# ptc.net
KiCad netlist of a schematic drawn in EasyEDA Pro
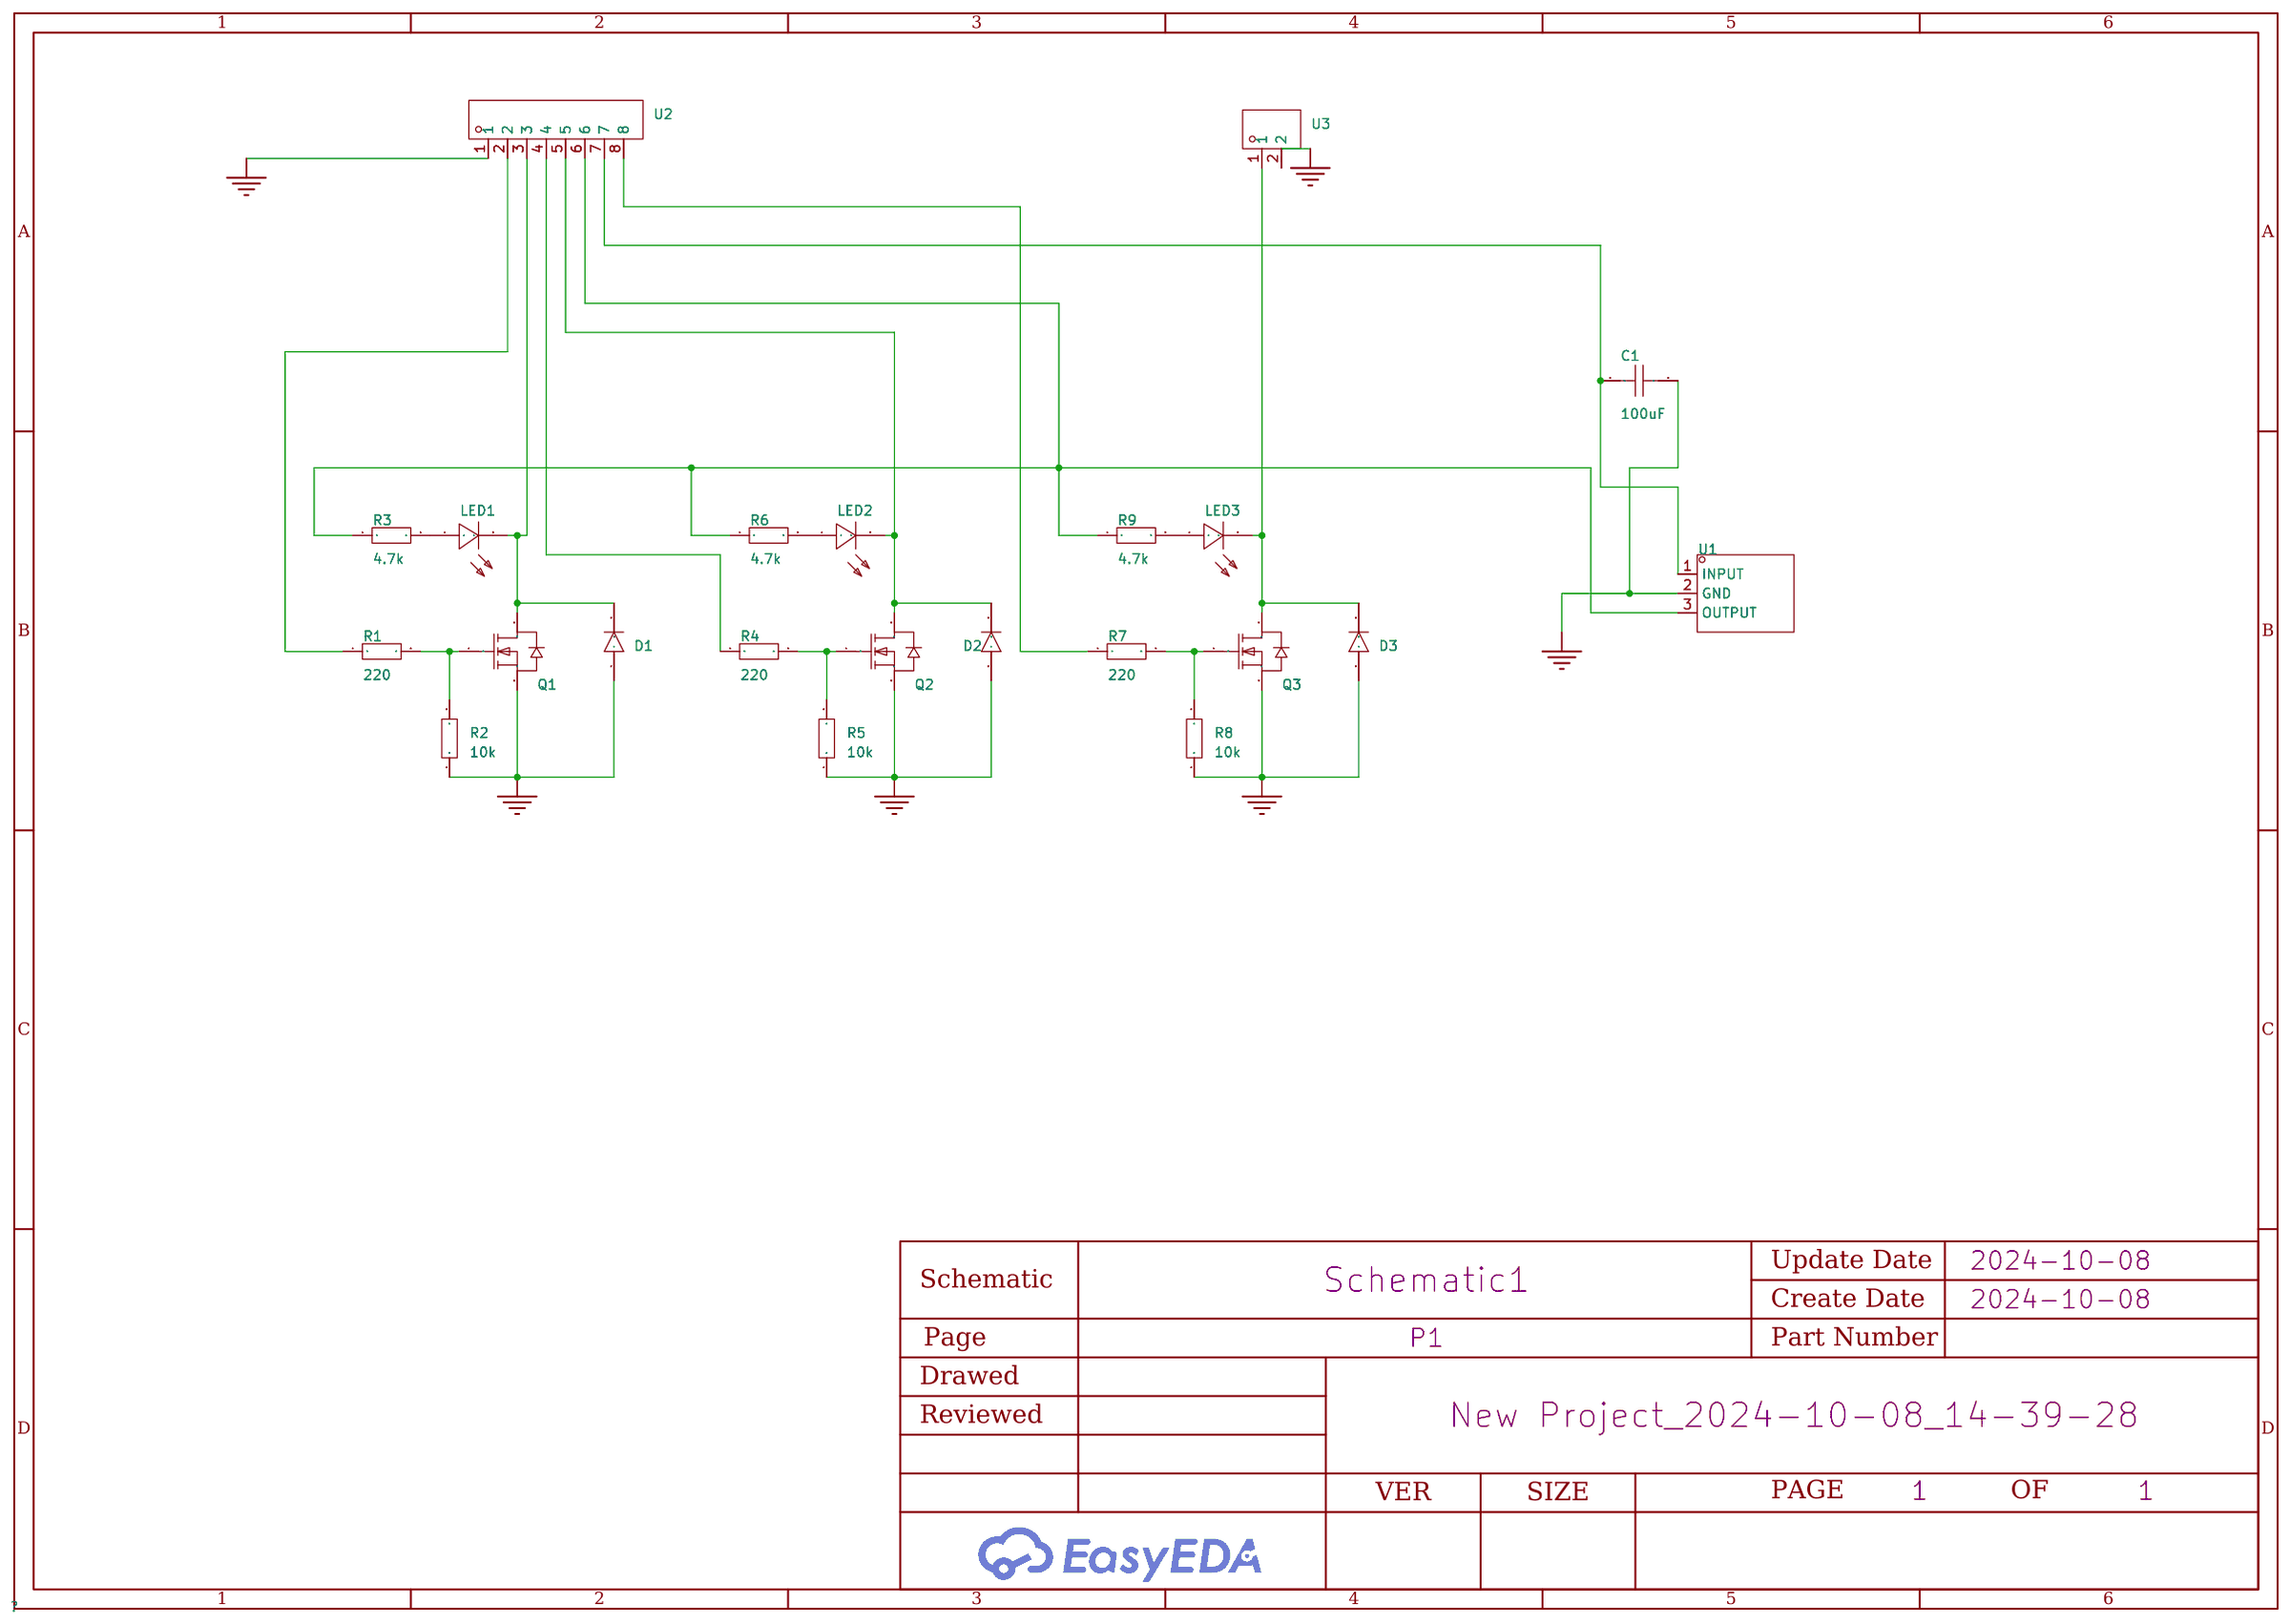
[diagram p0: schematic sheet]

(export (version "E")
  (design (tool "Eeschema 10.0.6"))
  (components
    (comp (ref "C1")
      (value "100uF")
      (footprint "easyedapro:C0603")
      (libsource (lib "easyedapro") (part "CapAcitance"))
    )
    (comp (ref "D1")
      (value "~")
      (footprint "easyedapro:DO-41_BD2.4-L4.7-P8.70-D0.9-RD")
      (fields (field (name "Manufacturer Part") "1N4007") (field (name "Manufacturer") "星海"))
      (libsource (lib "easyedapro") (part "1N4007-C84641"))
    )
    (comp (ref "D2")
      (value "~")
      (footprint "easyedapro:DO-41_BD2.4-L4.7-P8.70-D0.9-RD")
      (fields (field (name "Manufacturer Part") "1N4007") (field (name "Manufacturer") "星海"))
      (libsource (lib "easyedapro") (part "1N4007-C84641"))
    )
    (comp (ref "D3")
      (value "~")
      (footprint "easyedapro:DO-41_BD2.4-L4.7-P8.70-D0.9-RD")
      (fields (field (name "Manufacturer Part") "1N4007") (field (name "Manufacturer") "星海"))
      (libsource (lib "easyedapro") (part "1N4007-C84641"))
    )
    (comp (ref "LED1")
      (value "~")
      (footprint "easyedapro:LED0603-R-RD_RED")
      (fields
        (field (name "Manufacturer Part") "TJ-S1608SW6TGLC2R-A5")
        (field (name "Manufacturer") "TOGIALED(台湾统佳)")
      )
      (libsource (lib "easyedapro") (part "TJ-S1608SW6TGLC2R-A5"))
    )
    (comp (ref "LED2")
      (value "~")
      (footprint "easyedapro:LED0603-R-RD_RED")
      (fields
        (field (name "Manufacturer Part") "TJ-S1608SW6TGLC2R-A5")
        (field (name "Manufacturer") "TOGIALED(台湾统佳)")
      )
      (libsource (lib "easyedapro") (part "TJ-S1608SW6TGLC2R-A5"))
    )
    (comp (ref "LED3")
      (value "~")
      (footprint "easyedapro:LED0603-R-RD_RED")
      (fields
        (field (name "Manufacturer Part") "TJ-S1608SW6TGLC2R-A5")
        (field (name "Manufacturer") "TOGIALED(台湾统佳)")
      )
      (libsource (lib "easyedapro") (part "TJ-S1608SW6TGLC2R-A5"))
    )
    (comp (ref "Q1")
      (value "~")
      (footprint "easyedapro:TO-220-3_L10.0-W4.5-P2.54-L")
      (fields (field (name "Manufacturer Part") "IRFZ44NPBF") (field (name "Manufacturer") "Infineon(英飞凌)"))
      (libsource (lib "easyedapro") (part "IRFZ44NPBF"))
    )
    (comp (ref "Q2")
      (value "~")
      (footprint "easyedapro:TO-220-3_L10.0-W4.5-P2.54-L")
      (fields (field (name "Manufacturer Part") "IRFZ44NPBF") (field (name "Manufacturer") "Infineon(英飞凌)"))
      (libsource (lib "easyedapro") (part "IRFZ44NPBF"))
    )
    (comp (ref "Q3")
      (value "~")
      (footprint "easyedapro:TO-220-3_L10.0-W4.5-P2.54-L")
      (fields (field (name "Manufacturer Part") "IRFZ44NPBF") (field (name "Manufacturer") "Infineon(英飞凌)"))
      (libsource (lib "easyedapro") (part "IRFZ44NPBF"))
    )
    (comp (ref "R1")
      (value "220")
      (footprint "easyedapro:R0603")
      (fields
        (field (name "Manufacturer Part") "MFR0W8F1002A50")
        (field (name "Manufacturer") "UNI-ROYAL(厚声)")
      )
      (libsource (lib "easyedapro") (part "电阻"))
    )
    (comp (ref "R2")
      (value "10k")
      (footprint "easyedapro:R0603")
      (fields
        (field (name "Manufacturer Part") "MFR0W8F1002A50")
        (field (name "Manufacturer") "UNI-ROYAL(厚声)")
      )
      (libsource (lib "easyedapro") (part "电阻"))
    )
    (comp (ref "R3") (value "4.7k") (footprint "easyedapro:R0603") (libsource (lib "easyedapro") (part "电阻")))
    (comp (ref "R4")
      (value "220")
      (footprint "easyedapro:R0603")
      (fields
        (field (name "Manufacturer Part") "MFR0W8F1002A50")
        (field (name "Manufacturer") "UNI-ROYAL(厚声)")
      )
      (libsource (lib "easyedapro") (part "电阻"))
    )
    (comp (ref "R5")
      (value "10k")
      (footprint "easyedapro:R0603")
      (fields
        (field (name "Manufacturer Part") "MFR0W8F1002A50")
        (field (name "Manufacturer") "UNI-ROYAL(厚声)")
      )
      (libsource (lib "easyedapro") (part "电阻"))
    )
    (comp (ref "R6") (value "4.7k") (footprint "easyedapro:R0603") (libsource (lib "easyedapro") (part "电阻")))
    (comp (ref "R7")
      (value "220")
      (footprint "easyedapro:R0603")
      (fields
        (field (name "Manufacturer Part") "MFR0W8F1002A50")
        (field (name "Manufacturer") "UNI-ROYAL(厚声)")
      )
      (libsource (lib "easyedapro") (part "电阻"))
    )
    (comp (ref "R8")
      (value "10k")
      (footprint "easyedapro:R0603")
      (fields
        (field (name "Manufacturer Part") "MFR0W8F1002A50")
        (field (name "Manufacturer") "UNI-ROYAL(厚声)")
      )
      (libsource (lib "easyedapro") (part "电阻"))
    )
    (comp (ref "R9") (value "4.7k") (footprint "easyedapro:R0603") (libsource (lib "easyedapro") (part "电阻")))
    (comp (ref "U1")
      (value "~")
      (footprint "easyedapro:TO-252-2_L6.6-W6.1-P4.57-LS9.9-BR-CW")
      (fields (field (name "Manufacturer Part") "MC7812BDTG") (field (name "Manufacturer") "onsemi(安森美)"))
      (libsource (lib "easyedapro") (part "MC7812BDTG"))
    )
    (comp (ref "U2")
      (value "~")
      (footprint "easyedapro:CONN-TH_8P-P5.00_DB128V-5.0-8P")
      (fields
        (field (name "Manufacturer Part") "DB128V-5.0-8P-GN-S")
        (field (name "Manufacturer") "DIBO(地博电气)")
      )
      (libsource (lib "easyedapro") (part "DB128V-5.0-8P"))
    )
    (comp (ref "U3")
      (value "~")
      (footprint "easyedapro:CONN-TH_2P-P5.00_DB128V-5.0-2P")
      (fields
        (field (name "Manufacturer Part") "DB128V-5.0-2P-GN-S")
        (field (name "Manufacturer") "DIBO(地博电气)")
      )
      (libsource (lib "easyedapro") (part "DB128V-5.0-2P"))
    )
  )
  (nets
    (net (code "1") (name "GND") (class "Default")
      (node (ref "C1") (pin "2") (pinfunction "2_2") (pintype "input"))
      (node (ref "D1") (pin "2") (pinfunction "A_2") (pintype "input"))
      (node (ref "D2") (pin "2") (pinfunction "A_2") (pintype "input"))
      (node (ref "D3") (pin "2") (pinfunction "A_2") (pintype "input"))
      (node (ref "Q1") (pin "3") (pinfunction "S_3") (pintype "input"))
      (node (ref "Q2") (pin "3") (pinfunction "S_3") (pintype "input"))
      (node (ref "Q3") (pin "3") (pinfunction "S_3") (pintype "input"))
      (node (ref "R2") (pin "1") (pinfunction "1_1") (pintype "input"))
      (node (ref "R5") (pin "1") (pinfunction "1_1") (pintype "input"))
      (node (ref "R8") (pin "1") (pinfunction "1_1") (pintype "input"))
      (node (ref "U1") (pin "2") (pinfunction "GND_2") (pintype "input"))
      (node (ref "U2") (pin "1") (pinfunction "1_1") (pintype "input"))
      (node (ref "U3") (pin "2") (pinfunction "2_2") (pintype "input"))
    )
    (net (code "2") (name "Net-(D1-C)") (class "Default")
      (node (ref "D1") (pin "1") (pinfunction "C_1") (pintype "input"))
      (node (ref "LED1") (pin "2") (pinfunction "K_2") (pintype "input"))
      (node (ref "Q1") (pin "2") (pinfunction "D_2") (pintype "input"))
      (node (ref "U2") (pin "3") (pinfunction "3_3") (pintype "input"))
    )
    (net (code "3") (name "Net-(D2-C)") (class "Default")
      (node (ref "D2") (pin "1") (pinfunction "C_1") (pintype "input"))
      (node (ref "LED2") (pin "2") (pinfunction "K_2") (pintype "input"))
      (node (ref "Q2") (pin "2") (pinfunction "D_2") (pintype "input"))
      (node (ref "U2") (pin "5") (pinfunction "5_5") (pintype "input"))
    )
    (net (code "4") (name "Net-(D3-C)") (class "Default")
      (node (ref "D3") (pin "1") (pinfunction "C_1") (pintype "input"))
      (node (ref "LED3") (pin "2") (pinfunction "K_2") (pintype "input"))
      (node (ref "Q3") (pin "2") (pinfunction "D_2") (pintype "input"))
      (node (ref "U3") (pin "1") (pinfunction "1_1") (pintype "input"))
    )
    (net (code "5") (name "Net-(LED1-A)") (class "Default")
      (node (ref "LED1") (pin "1") (pinfunction "A_1") (pintype "input"))
      (node (ref "R3") (pin "2") (pinfunction "2_2") (pintype "input"))
    )
    (net (code "6") (name "Net-(LED2-A)") (class "Default")
      (node (ref "LED2") (pin "1") (pinfunction "A_1") (pintype "input"))
      (node (ref "R6") (pin "2") (pinfunction "2_2") (pintype "input"))
    )
    (net (code "7") (name "Net-(LED3-A)") (class "Default")
      (node (ref "LED3") (pin "1") (pinfunction "A_1") (pintype "input"))
      (node (ref "R9") (pin "2") (pinfunction "2_2") (pintype "input"))
    )
    (net (code "8") (name "Net-(Q1-G)") (class "Default")
      (node (ref "Q1") (pin "1") (pinfunction "G_1") (pintype "input"))
      (node (ref "R1") (pin "2") (pinfunction "2_2") (pintype "input"))
      (node (ref "R2") (pin "2") (pinfunction "2_2") (pintype "input"))
    )
    (net (code "9") (name "Net-(Q2-G)") (class "Default")
      (node (ref "Q2") (pin "1") (pinfunction "G_1") (pintype "input"))
      (node (ref "R4") (pin "2") (pinfunction "2_2") (pintype "input"))
      (node (ref "R5") (pin "2") (pinfunction "2_2") (pintype "input"))
    )
    (net (code "10") (name "Net-(Q3-G)") (class "Default")
      (node (ref "Q3") (pin "1") (pinfunction "G_1") (pintype "input"))
      (node (ref "R7") (pin "2") (pinfunction "2_2") (pintype "input"))
      (node (ref "R8") (pin "2") (pinfunction "2_2") (pintype "input"))
    )
    (net (code "11") (name "Net-(R1-Pad1)") (class "Default")
      (node (ref "R1") (pin "1") (pinfunction "1_1") (pintype "input"))
      (node (ref "U2") (pin "2") (pinfunction "2_2") (pintype "input"))
    )
    (net (code "12") (name "Net-(R4-Pad1)") (class "Default")
      (node (ref "R4") (pin "1") (pinfunction "1_1") (pintype "input"))
      (node (ref "U2") (pin "4") (pinfunction "4_4") (pintype "input"))
    )
    (net (code "13") (name "Net-(R7-Pad1)") (class "Default")
      (node (ref "R7") (pin "1") (pinfunction "1_1") (pintype "input"))
      (node (ref "U2") (pin "8") (pinfunction "8_8") (pintype "input"))
    )
    (net (code "14") (name "Net-(U1-INPUT)") (class "Default")
      (node (ref "C1") (pin "1") (pinfunction "1_1") (pintype "input"))
      (node (ref "U1") (pin "1") (pinfunction "INPUT_1") (pintype "input"))
      (node (ref "U2") (pin "7") (pinfunction "7_7") (pintype "input"))
    )
    (net (code "15") (name "Net-(U1-OUTPUT)") (class "Default")
      (node (ref "R3") (pin "1") (pinfunction "1_1") (pintype "input"))
      (node (ref "R6") (pin "1") (pinfunction "1_1") (pintype "input"))
      (node (ref "R9") (pin "1") (pinfunction "1_1") (pintype "input"))
      (node (ref "U1") (pin "3") (pinfunction "OUTPUT_3") (pintype "input"))
      (node (ref "U2") (pin "6") (pinfunction "6_6") (pintype "input"))
    )
  )
)
